# usb_tester-2_01.net
KiCad netlist of a schematic drawn in EAGLE
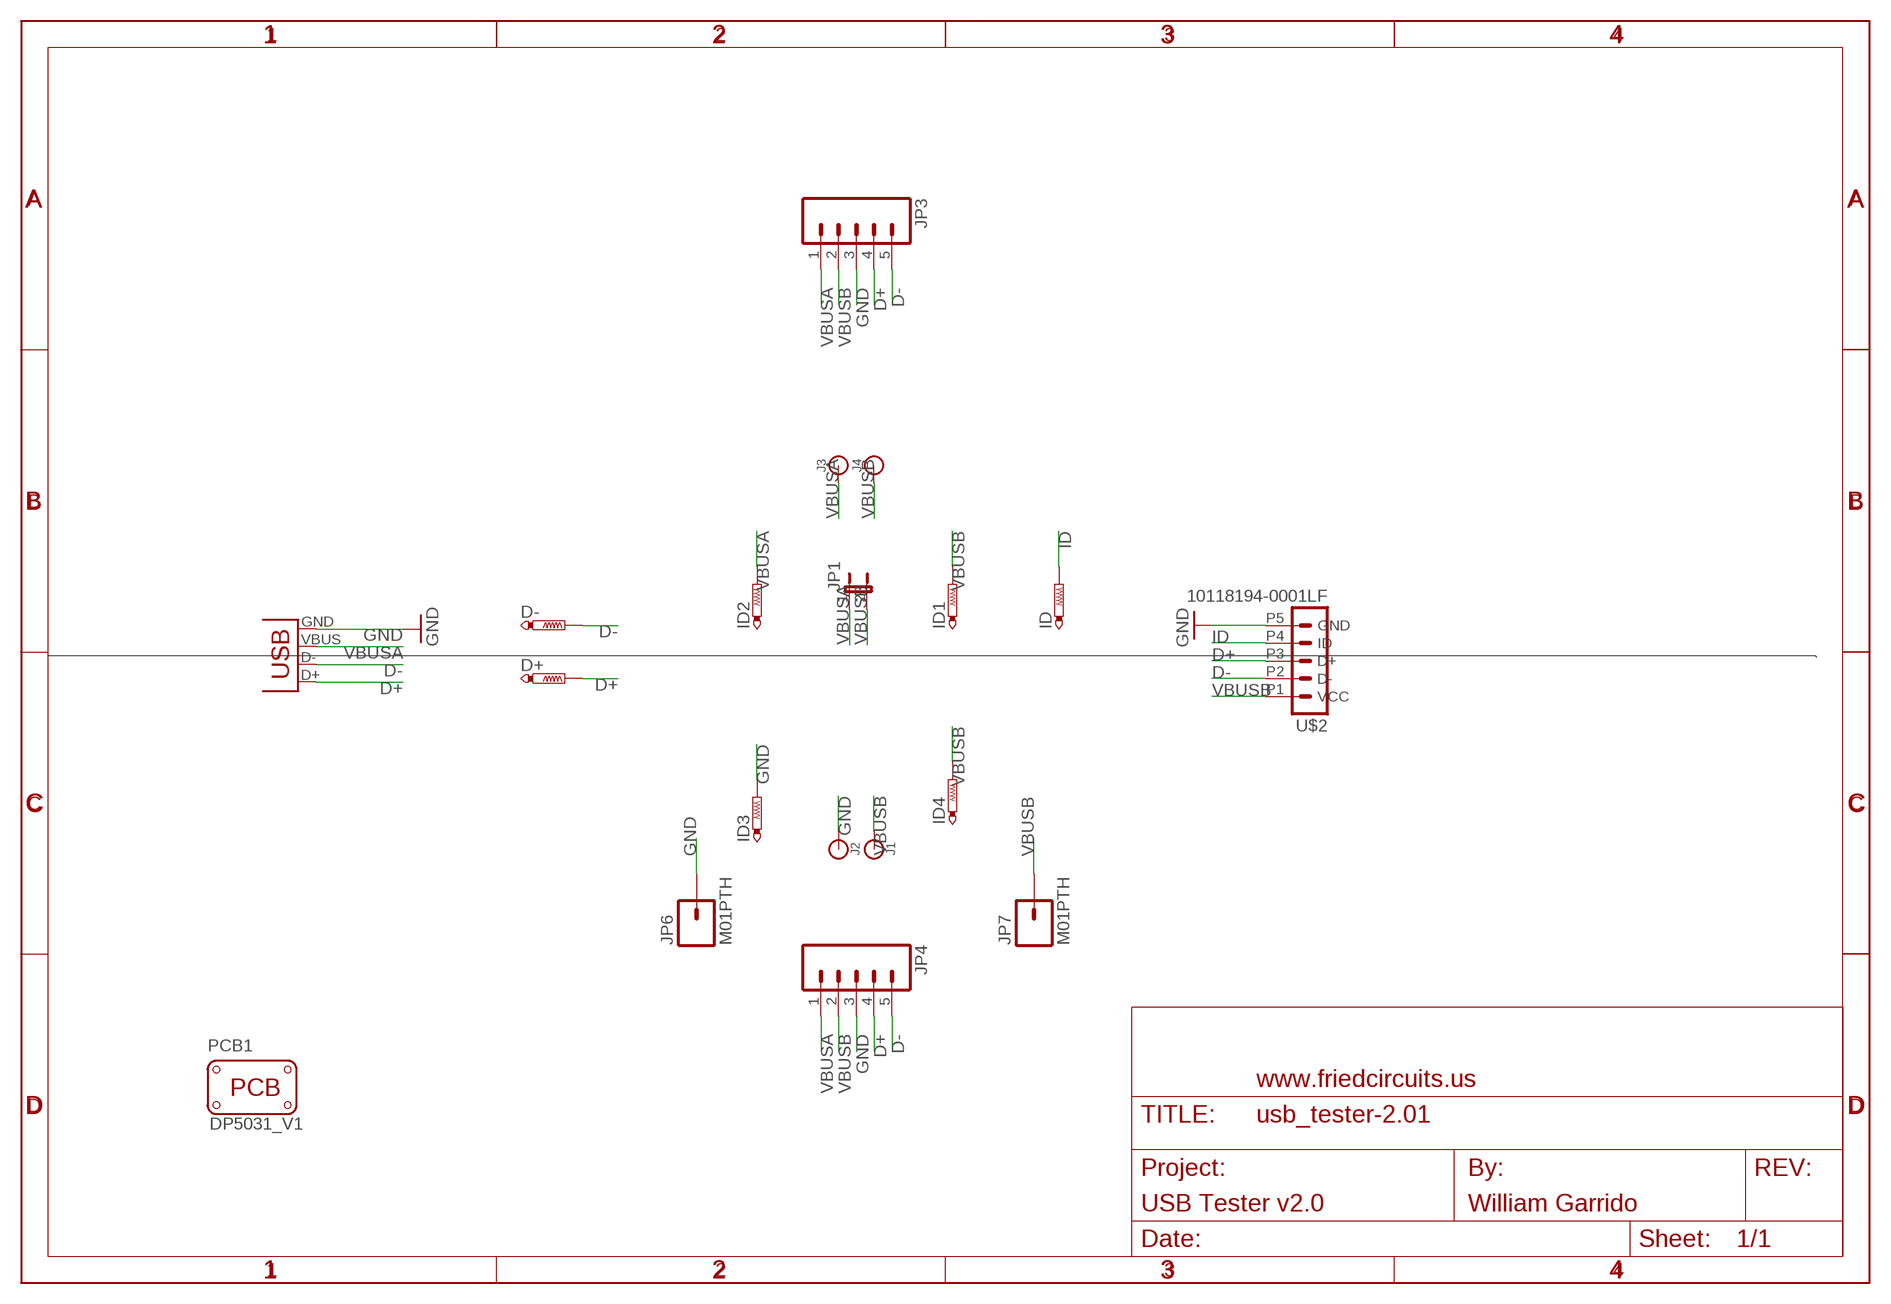
[diagram p0: schematic, sheet 1]

(export (version "E")
  (design (tool "Eeschema 10.0.6"))
  (components
    (comp (ref "D+")
      (value "PTR1PAD1-20")
      (footprint "eagle-import:P1-20")
      (libsource (lib "eagle-import") (part "PTR1PAD1-20"))
    )
    (comp (ref "D-")
      (value "PTR1PAD1-20")
      (footprint "eagle-import:P1-20")
      (libsource (lib "eagle-import") (part "PTR1PAD1-20"))
    )
    (comp (ref "ID")
      (value "PTR1PAD1-20")
      (footprint "eagle-import:P1-20")
      (libsource (lib "eagle-import") (part "PTR1PAD1-20"))
    )
    (comp (ref "ID1")
      (value "PTR1PAD1-20")
      (footprint "eagle-import:P1-20")
      (libsource (lib "eagle-import") (part "PTR1PAD1-20"))
    )
    (comp (ref "ID2")
      (value "PTR1PAD1-20")
      (footprint "eagle-import:P1-20")
      (libsource (lib "eagle-import") (part "PTR1PAD1-20"))
    )
    (comp (ref "ID3")
      (value "PTR1PAD1-20")
      (footprint "eagle-import:P1-20")
      (libsource (lib "eagle-import") (part "PTR1PAD1-20"))
    )
    (comp (ref "ID4")
      (value "PTR1PAD1-20")
      (footprint "eagle-import:P1-20")
      (libsource (lib "eagle-import") (part "PTR1PAD1-20"))
    )
    (comp (ref "J1")
      (value "BANANA_CONN")
      (footprint "eagle-import:BANANA_CONN")
      (libsource (lib "eagle-import") (part "BANANA_CONN"))
    )
    (comp (ref "J2")
      (value "BANANA_CONN")
      (footprint "eagle-import:BANANA_CONN")
      (libsource (lib "eagle-import") (part "BANANA_CONN"))
    )
    (comp (ref "J3")
      (value "BANANA_CONN")
      (footprint "eagle-import:BANANA_CONN")
      (libsource (lib "eagle-import") (part "BANANA_CONN"))
    )
    (comp (ref "J4")
      (value "BANANA_CONN")
      (footprint "eagle-import:BANANA_CONN")
      (libsource (lib "eagle-import") (part "BANANA_CONN"))
    )
    (comp (ref "JP1")
      (value "JUMPER-2PTH_LOCK")
      (footprint "eagle-import:1X02_LOCK")
      (libsource (lib "eagle-import") (part "JUMPER-2PTH_LOCK"))
    )
    (comp (ref "JP3")
      (value "M05LOCK")
      (footprint "eagle-import:1X05_LOCK")
      (libsource (lib "eagle-import") (part "M05LOCK"))
    )
    (comp (ref "JP4")
      (value "M05LOCK")
      (footprint "eagle-import:1X05_LOCK")
      (libsource (lib "eagle-import") (part "M05LOCK"))
    )
    (comp (ref "JP6")
      (value "M01PTH")
      (footprint "eagle-import:1X01")
      (libsource (lib "eagle-import") (part "M01PTH"))
    )
    (comp (ref "JP7")
      (value "M01PTH")
      (footprint "eagle-import:1X01")
      (libsource (lib "eagle-import") (part "M01PTH"))
    )
    (comp (ref "PCB1")
      (value "PCB_DP_RECTANGLE-31X50")
      (footprint "eagle-import:DP5031_V1")
      (libsource (lib "eagle-import") (part "PCB_DP_RECTANGLE-31X50"))
    )
    (comp (ref "U$1")
      (value "FRAME_DINA4_L")
      (footprint "eagle-import:FC_CREDIT")
      (fields
        (field (name "AUTHOR") "William Garrido")
        (field (name "FF3") "friedcircuits.us")
        (field (name "PROJECT") "USB Tester v2.0")
      )
      (libsource (lib "eagle-import") (part "FRAME_DINA4_L"))
    )
    (comp (ref "U$2")
      (value "10118194-0001LF")
      (footprint "eagle-import:10118194-0001LF")
      (libsource (lib "eagle-import") (part "10118194-0001LF"))
    )
    (comp (ref "USB-DEVICE")
      (value "USB-A-SMD")
      (footprint "eagle-import:USB-A-S-NOSILK-FEMALE")
      (libsource (lib "eagle-import") (part "USB-A-SMD"))
    )
  )
  (nets
    (net (code "1") (name "/D+") (class "Default")
      (node (ref "D+") (pin "TP") (pinfunction "TP_TP") (pintype "input"))
      (node (ref "JP3") (pin "4") (pinfunction "4_4") (pintype "passive"))
      (node (ref "JP4") (pin "4") (pinfunction "4_4") (pintype "passive"))
      (node (ref "U$2") (pin "P3") (pinfunction "D+_P3") (pintype "passive"))
      (node (ref "USB-DEVICE") (pin "D+") (pinfunction "D+_D+") (pintype "bidirectional"))
    )
    (net (code "2") (name "/D-") (class "Default")
      (node (ref "D-") (pin "TP") (pinfunction "TP_TP") (pintype "input"))
      (node (ref "JP3") (pin "5") (pinfunction "5_5") (pintype "passive"))
      (node (ref "JP4") (pin "5") (pinfunction "5_5") (pintype "passive"))
      (node (ref "U$2") (pin "P2") (pinfunction "D-_P2") (pintype "passive"))
      (node (ref "USB-DEVICE") (pin "D-") (pinfunction "D-_D-") (pintype "bidirectional"))
    )
    (net (code "3") (name "/ID") (class "Default")
      (node (ref "ID") (pin "TP") (pinfunction "TP_TP") (pintype "input"))
      (node (ref "U$2") (pin "P4") (pinfunction "ID_P4") (pintype "passive"))
    )
    (net (code "4") (name "/VBUSA") (class "Default")
      (node (ref "ID2") (pin "TP") (pinfunction "TP_TP") (pintype "input"))
      (node (ref "J3") (pin "P$1") (pinfunction "1_P$1") (pintype "passive"))
      (node (ref "JP1") (pin "1") (pinfunction "1_1") (pintype "passive"))
      (node (ref "JP3") (pin "1") (pinfunction "1_1") (pintype "passive"))
      (node (ref "JP4") (pin "1") (pinfunction "1_1") (pintype "passive"))
      (node (ref "USB-DEVICE") (pin "VBUS") (pinfunction "VBUS_VBUS") (pintype "bidirectional"))
    )
    (net (code "5") (name "/VBUSB") (class "Default")
      (node (ref "ID1") (pin "TP") (pinfunction "TP_TP") (pintype "input"))
      (node (ref "ID4") (pin "TP") (pinfunction "TP_TP") (pintype "input"))
      (node (ref "J1") (pin "P$1") (pinfunction "1_P$1") (pintype "passive"))
      (node (ref "J4") (pin "P$1") (pinfunction "1_P$1") (pintype "passive"))
      (node (ref "JP1") (pin "2") (pinfunction "2_2") (pintype "passive"))
      (node (ref "JP3") (pin "2") (pinfunction "2_2") (pintype "passive"))
      (node (ref "JP4") (pin "2") (pinfunction "2_2") (pintype "passive"))
      (node (ref "JP7") (pin "1") (pinfunction "1_1") (pintype "passive"))
      (node (ref "U$2") (pin "P1") (pinfunction "VCC_P1") (pintype "passive"))
    )
    (net (code "6") (name "GND") (class "Default")
      (node (ref "ID3") (pin "TP") (pinfunction "TP_TP") (pintype "input"))
      (node (ref "J2") (pin "P$1") (pinfunction "1_P$1") (pintype "passive"))
      (node (ref "JP3") (pin "3") (pinfunction "3_3") (pintype "passive"))
      (node (ref "JP4") (pin "3") (pinfunction "3_3") (pintype "passive"))
      (node (ref "JP6") (pin "1") (pinfunction "1_1") (pintype "passive"))
      (node (ref "U$2") (pin "P5") (pinfunction "GND_P5") (pintype "passive"))
      (node (ref "USB-DEVICE") (pin "GND") (pinfunction "GND_GND") (pintype "bidirectional"))
    )
  )
)
